# SCH_jlh1969_2026-03-17.net
KiCad netlist of a schematic drawn in EasyEDA
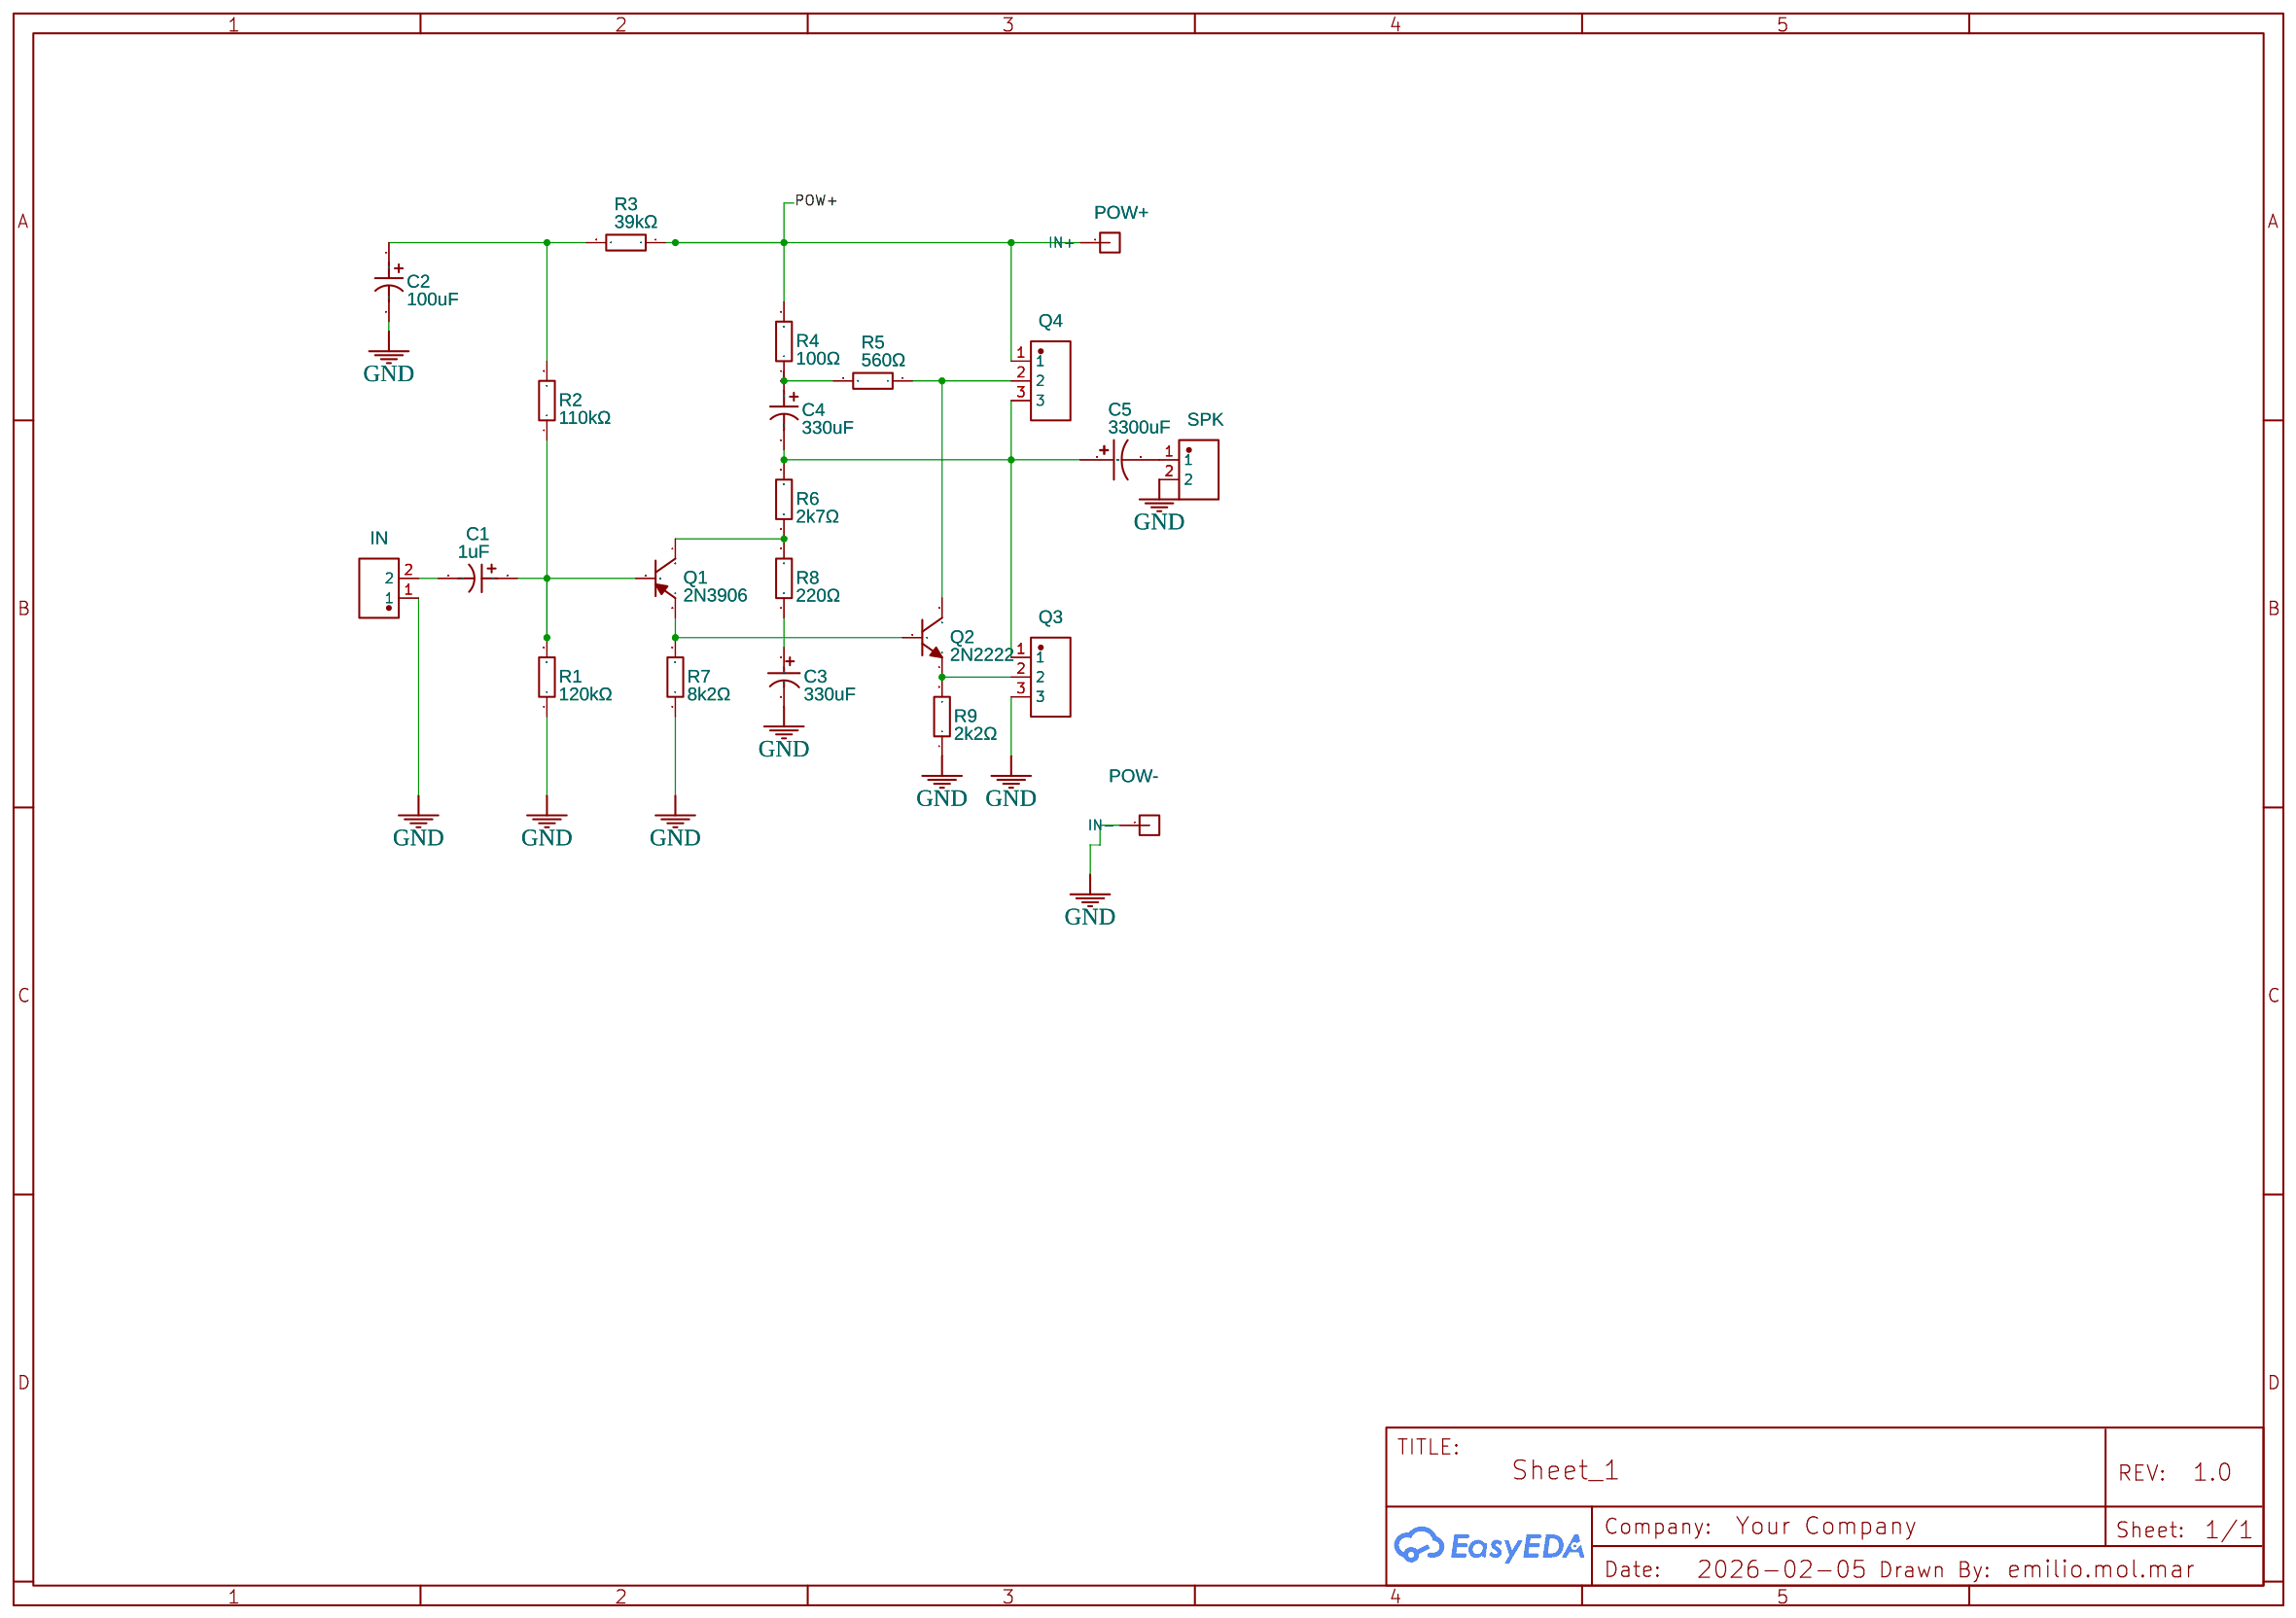
[diagram p0: schematic sheet]

(export (version "E")
  (design (tool "Eeschema 10.0.6"))
  (components
    (comp (ref "C1")
      (value "1uF")
      (fields (field (name "Manufacturer Part") "WL1H105M05011PC") (field (name "Manufacturer") "SAMWHA(三和)"))
      (libsource (lib "") (part "WL1H105M05011PC"))
    )
    (comp (ref "C2")
      (value "100uF")
      (fields (field (name "Manufacturer Part") "GR1V101M0611") (field (name "Manufacturer") "ROQANG(容强)"))
      (libsource (lib "") (part "GR1V101M0611"))
    )
    (comp (ref "C3")
      (value "330uF")
      (fields
        (field (name "Manufacturer Part") "25YXF220MEFCT78X11.5")
        (field (name "Manufacturer") "Rubycon(红宝石)")
      )
      (libsource (lib "") (part "25YXF220MEFCT78X11.5"))
    )
    (comp (ref "C4")
      (value "330uF")
      (fields (field (name "Manufacturer Part") "GR1V101M0611") (field (name "Manufacturer") "ROQANG(容强)"))
      (libsource (lib "") (part "GR1V101M0611_1"))
    )
    (comp (ref "C5")
      (value "3300uF")
      (fields
        (field (name "Manufacturer Part") "35YXF3300MEFCGC18X35.5")
        (field (name "Manufacturer") "Rubycon(红宝石)")
      )
      (libsource (lib "") (part "35YXF3300MEFCGC18X35.5"))
    )
    (comp (ref "IN")
      (value "XDZ200-1-02-Z-2.0-G1")
      (fields (field (name "Manufacturer") "XUNDA(讯答)"))
      (libsource (lib "") (part "XDZ200-1-02-Z-2.0-G1_1"))
    )
    (comp (ref "POW+")
      (value "Buck_IN+")
      (fields (field (name "Manufacturer Part") "HDR-TH_1P-P2.54-V-M"))
      (libsource (lib "") (part "Header_1Pin_1"))
    )
    (comp (ref "POW-")
      (value "Buck_IN-")
      (fields (field (name "Manufacturer Part") "HDR-TH_1P-P2.54-V-M"))
      (libsource (lib "") (part "Header_1Pin"))
    )
    (comp (ref "Q1")
      (value "2N3906")
      (fields (field (name "Manufacturer") "Slkor(萨科微)"))
      (libsource (lib "") (part "2N3906_C2980868"))
    )
    (comp (ref "Q2")
      (value "2N2222")
      (fields (field (name "Manufacturer") "Solid State System"))
      (libsource (lib "") (part "2N2222_C6996955"))
    )
    (comp (ref "Q3")
      (value "PEC03SAAN_C5708637")
      (fields (field (name "Manufacturer Part") "PEC03SAAN") (field (name "Manufacturer") "Sullins"))
      (libsource (lib "") (part "PEC03SAAN_C5708637"))
    )
    (comp (ref "Q4")
      (value "PEC03SAAN_C5708637")
      (fields (field (name "Manufacturer Part") "PEC03SAAN") (field (name "Manufacturer") "Sullins"))
      (libsource (lib "") (part "PEC03SAAN_C5708637"))
    )
    (comp (ref "R1")
      (value "120kΩ")
      (fields
        (field (name "Manufacturer Part") "CF1/4W-110KΩ±5% T52")
        (field (name "Manufacturer") "CCO(千志电子)")
      )
      (libsource (lib "") (part "CF1/4W-110KΩ±5% T52"))
    )
    (comp (ref "R2")
      (value "110kΩ")
      (fields
        (field (name "Manufacturer Part") "CF1/4W-110KΩ±5% T52")
        (field (name "Manufacturer") "CCO(千志电子)")
      )
      (libsource (lib "") (part "CF1/4W-110KΩ±5% T52"))
    )
    (comp (ref "R3")
      (value "39kΩ")
      (fields
        (field (name "Manufacturer Part") "CF1/4W-110KΩ±5% T52")
        (field (name "Manufacturer") "CCO(千志电子)")
      )
      (libsource (lib "") (part "CF1/4W-110KΩ±5% T52_1"))
    )
    (comp (ref "R4")
      (value "100Ω")
      (fields
        (field (name "Manufacturer Part") "CF1/4W-110KΩ±5% T52")
        (field (name "Manufacturer") "CCO(千志电子)")
      )
      (libsource (lib "") (part "CF1/4W-110KΩ±5% T52"))
    )
    (comp (ref "R5")
      (value "560Ω")
      (fields
        (field (name "Manufacturer Part") "CF1/4W-110KΩ±5% T52")
        (field (name "Manufacturer") "CCO(千志电子)")
      )
      (libsource (lib "") (part "CF1/4W-110KΩ±5% T52_1"))
    )
    (comp (ref "R6")
      (value "2k7Ω")
      (fields
        (field (name "Manufacturer Part") "CF1/4W-110KΩ±5% T52")
        (field (name "Manufacturer") "CCO(千志电子)")
      )
      (libsource (lib "") (part "CF1/4W-110KΩ±5% T52"))
    )
    (comp (ref "R7")
      (value "8k2Ω")
      (fields
        (field (name "Manufacturer Part") "CF1/4W-110KΩ±5% T52")
        (field (name "Manufacturer") "CCO(千志电子)")
      )
      (libsource (lib "") (part "CF1/4W-110KΩ±5% T52"))
    )
    (comp (ref "R8")
      (value "220Ω")
      (fields
        (field (name "Manufacturer Part") "CF1/4W-110KΩ±5% T52")
        (field (name "Manufacturer") "CCO(千志电子)")
      )
      (libsource (lib "") (part "CF1/4W-110KΩ±5% T52"))
    )
    (comp (ref "R9")
      (value "2k2Ω")
      (fields
        (field (name "Manufacturer Part") "CF1/4W-110KΩ±5% T52")
        (field (name "Manufacturer") "CCO(千志电子)")
      )
      (libsource (lib "") (part "CF1/4W-110KΩ±5% T52"))
    )
    (comp (ref "SPK")
      (value "XDZ200-1-02-Z-2.0-G1")
      (fields (field (name "Manufacturer") "XUNDA(讯答)"))
      (libsource (lib "") (part "XDZ200-1-02-Z-2.0-G1"))
    )
  )
  (nets
    (net (code "1") (name "/POW+") (class "Default")
      (node (ref "POW+") (pin "1") (pinfunction "IN+_1") (pintype "unspecified"))
      (node (ref "Q4") (pin "1") (pinfunction "1_1") (pintype "unspecified"))
      (node (ref "R3") (pin "1") (pinfunction "1_1") (pintype "unspecified"))
      (node (ref "R4") (pin "2") (pinfunction "2_2") (pintype "unspecified"))
    )
    (net (code "2") (name "GND") (class "Default")
      (node (ref "C2") (pin "2") (pinfunction "2_2") (pintype "input"))
      (node (ref "C3") (pin "2") (pinfunction "2_2") (pintype "input"))
      (node (ref "IN") (pin "1") (pinfunction "1_1") (pintype "unspecified"))
      (node (ref "POW-") (pin "1") (pinfunction "IN-_1") (pintype "unspecified"))
      (node (ref "Q3") (pin "3") (pinfunction "3_3") (pintype "unspecified"))
      (node (ref "R1") (pin "1") (pinfunction "1_1") (pintype "unspecified"))
      (node (ref "R7") (pin "1") (pinfunction "1_1") (pintype "unspecified"))
      (node (ref "R9") (pin "1") (pinfunction "1_1") (pintype "unspecified"))
      (node (ref "SPK") (pin "2") (pinfunction "2_2") (pintype "unspecified"))
    )
    (net (code "3") (name "Net-(C1-Pad2)") (class "Default")
      (node (ref "C1") (pin "2") (pinfunction "2_2") (pintype "input"))
      (node (ref "IN") (pin "2") (pinfunction "2_2") (pintype "unspecified"))
    )
    (net (code "4") (name "Net-(C2-Pad1)") (class "Default")
      (node (ref "C2") (pin "1") (pinfunction "1_1") (pintype "input"))
      (node (ref "R2") (pin "2") (pinfunction "2_2") (pintype "unspecified"))
      (node (ref "R3") (pin "2") (pinfunction "2_2") (pintype "unspecified"))
    )
    (net (code "5") (name "Net-(C3-Pad1)") (class "Default")
      (node (ref "C3") (pin "1") (pinfunction "1_1") (pintype "input"))
      (node (ref "R8") (pin "1") (pinfunction "1_1") (pintype "unspecified"))
    )
    (net (code "6") (name "Net-(C4-Pad1)") (class "Default")
      (node (ref "C4") (pin "1") (pinfunction "1_1") (pintype "input"))
      (node (ref "R4") (pin "1") (pinfunction "1_1") (pintype "unspecified"))
      (node (ref "R5") (pin "2") (pinfunction "2_2") (pintype "unspecified"))
    )
    (net (code "7") (name "Net-(C4-Pad2)") (class "Default")
      (node (ref "C4") (pin "2") (pinfunction "2_2") (pintype "input"))
      (node (ref "C5") (pin "1") (pinfunction "1_1") (pintype "unspecified"))
      (node (ref "Q3") (pin "1") (pinfunction "1_1") (pintype "unspecified"))
      (node (ref "Q4") (pin "3") (pinfunction "3_3") (pintype "unspecified"))
      (node (ref "R6") (pin "2") (pinfunction "2_2") (pintype "unspecified"))
    )
    (net (code "8") (name "Net-(C5-Pad2)") (class "Default")
      (node (ref "C5") (pin "2") (pinfunction "2_2") (pintype "unspecified"))
      (node (ref "SPK") (pin "1") (pinfunction "1_1") (pintype "unspecified"))
    )
    (net (code "9") (name "Net-(Q1-B)") (class "Default")
      (node (ref "C1") (pin "1") (pinfunction "1_1") (pintype "input"))
      (node (ref "Q1") (pin "2") (pinfunction "B_2") (pintype "input"))
      (node (ref "R1") (pin "2") (pinfunction "2_2") (pintype "unspecified"))
      (node (ref "R2") (pin "1") (pinfunction "1_1") (pintype "unspecified"))
    )
    (net (code "10") (name "Net-(Q1-C)") (class "Default")
      (node (ref "Q1") (pin "1") (pinfunction "C_1") (pintype "input"))
      (node (ref "R6") (pin "1") (pinfunction "1_1") (pintype "unspecified"))
      (node (ref "R8") (pin "2") (pinfunction "2_2") (pintype "unspecified"))
    )
    (net (code "11") (name "Net-(Q1-E)") (class "Default")
      (node (ref "Q1") (pin "3") (pinfunction "E_3") (pintype "input"))
      (node (ref "Q2") (pin "2") (pinfunction "B_2") (pintype "input"))
      (node (ref "R7") (pin "2") (pinfunction "2_2") (pintype "unspecified"))
    )
    (net (code "12") (name "Net-(Q2-C)") (class "Default")
      (node (ref "Q2") (pin "3") (pinfunction "C_3") (pintype "input"))
      (node (ref "Q4") (pin "2") (pinfunction "2_2") (pintype "unspecified"))
      (node (ref "R5") (pin "1") (pinfunction "1_1") (pintype "unspecified"))
    )
    (net (code "13") (name "Net-(Q2-E)") (class "Default")
      (node (ref "Q2") (pin "1") (pinfunction "E_1") (pintype "input"))
      (node (ref "Q3") (pin "2") (pinfunction "2_2") (pintype "unspecified"))
      (node (ref "R9") (pin "2") (pinfunction "2_2") (pintype "unspecified"))
    )
  )
)
